# wk3.net
KiCad netlist of a schematic drawn in EAGLE
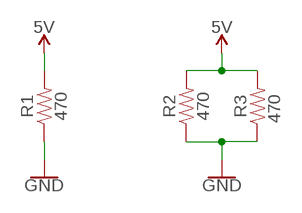
[diagram p0: schematic, sheet 1]

(export (version "E")
  (design (tool "Eeschema 10.0.6"))
  (components
    (comp (ref "R1")
      (value "470")
      (footprint "eagle-import:AXIAL-0.3")
      (libsource (lib "eagle-import") (part "RESISTORAXIAL-0.3"))
    )
    (comp (ref "R2")
      (value "470")
      (footprint "eagle-import:AXIAL-0.3")
      (libsource (lib "eagle-import") (part "RESISTORAXIAL-0.3"))
    )
    (comp (ref "R3")
      (value "470")
      (footprint "eagle-import:AXIAL-0.3")
      (libsource (lib "eagle-import") (part "RESISTORAXIAL-0.3"))
    )
  )
  (nets
    (net (code "1") (name "5V") (class "Default")
      (node (ref "R1") (pin "P$2") (pinfunction "2_P$2") (pintype "passive"))
      (node (ref "R2") (pin "P$2") (pinfunction "2_P$2") (pintype "passive"))
      (node (ref "R3") (pin "P$2") (pinfunction "2_P$2") (pintype "passive"))
    )
    (net (code "2") (name "GND") (class "Default")
      (node (ref "R1") (pin "P$1") (pinfunction "1_P$1") (pintype "passive"))
      (node (ref "R2") (pin "P$1") (pinfunction "1_P$1") (pintype "passive"))
      (node (ref "R3") (pin "P$1") (pinfunction "1_P$1") (pintype "passive"))
    )
  )
)
